# CB77-EI-Conversion-V1.net
KiCad netlist of a schematic drawn in EAGLE
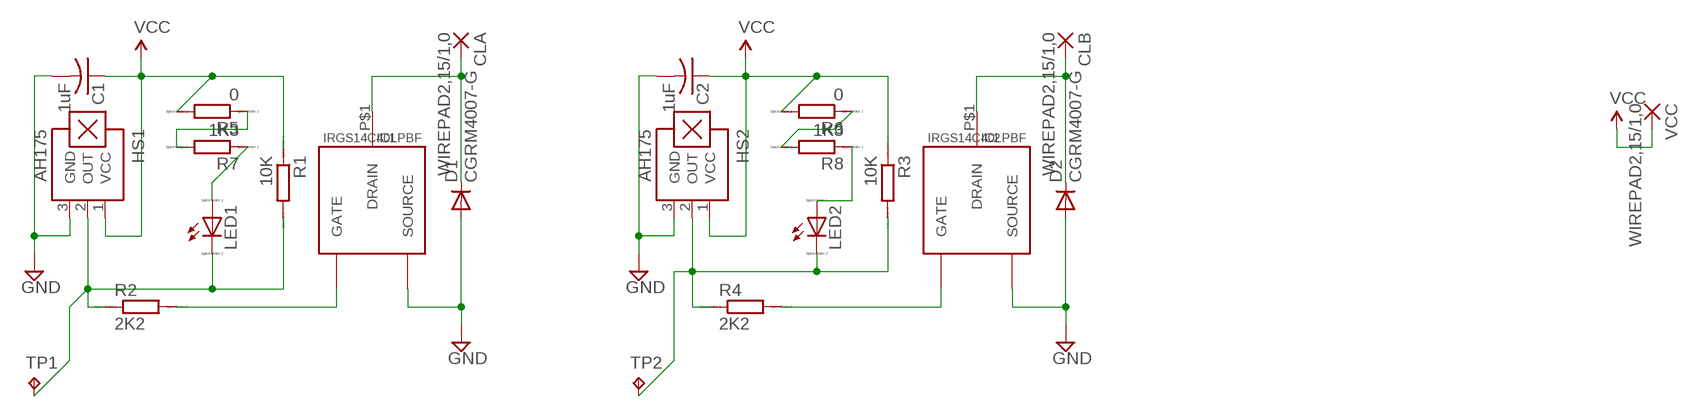
[diagram p0: schematic, sheet 1]

(export (version "E")
  (design (tool "Eeschema 10.0.6"))
  (components
    (comp (ref "C1")
      (value ".1uF")
      (footprint "eagle-import:C0603K")
      (libsource (lib "eagle-import") (part "C-USC0603K"))
    )
    (comp (ref "C2")
      (value ".1uF")
      (footprint "eagle-import:C0603K")
      (libsource (lib "eagle-import") (part "C-USC0603K"))
    )
    (comp (ref "CLA")
      (value "WIREPAD2,15/1,0")
      (footprint "eagle-import:2,15_1,0")
      (libsource (lib "eagle-import") (part "WIREPAD2,15/1,0"))
    )
    (comp (ref "CLB")
      (value "WIREPAD2,15/1,0")
      (footprint "eagle-import:2,15_1,0")
      (libsource (lib "eagle-import") (part "WIREPAD2,15/1,0"))
    )
    (comp (ref "D1")
      (value "CGRM4007-G")
      (footprint "eagle-import:SOD-123_MINI-SMA")
      (libsource (lib "eagle-import") (part "CGRM400-G7"))
    )
    (comp (ref "D2")
      (value "CGRM4007-G")
      (footprint "eagle-import:SOD-123_MINI-SMA")
      (libsource (lib "eagle-import") (part "CGRM400-G7"))
    )
    (comp (ref "HS1")
      (value "AH175")
      (footprint "eagle-import:SOT23-W")
      (fields (field (name "MF") "ALLEGRO MICROSYSTEMS, INC.") (field (name "MPN") "A1301ELHLT-T"))
      (libsource (lib "eagle-import") (part "A13?LH01"))
    )
    (comp (ref "HS2")
      (value "AH175")
      (footprint "eagle-import:SOT23-W")
      (fields (field (name "MF") "ALLEGRO MICROSYSTEMS, INC.") (field (name "MPN") "A1301ELHLT-T"))
      (libsource (lib "eagle-import") (part "A13?LH01"))
    )
    (comp (ref "IC1")
      (value "IRGS14C40LPBF")
      (footprint "eagle-import:TO-263AB")
      (libsource (lib "eagle-import") (part "IRGS14C40LPBF"))
    )
    (comp (ref "IC2")
      (value "IRGS14C40LPBF")
      (footprint "eagle-import:TO-263AB")
      (libsource (lib "eagle-import") (part "IRGS14C40LPBF"))
    )
    (comp (ref "LED1")
      (value "LED_E")
      (footprint "eagle-import:LED_1206")
      (libsource (lib "eagle-import") (part "LED_E"))
    )
    (comp (ref "LED2")
      (value "LED_E")
      (footprint "eagle-import:LED_1206")
      (libsource (lib "eagle-import") (part "LED_E"))
    )
    (comp (ref "R1")
      (value "10K")
      (footprint "eagle-import:R0805")
      (libsource (lib "eagle-import") (part "R"))
    )
    (comp (ref "R2")
      (value "2K2")
      (footprint "eagle-import:R0805")
      (libsource (lib "eagle-import") (part "R"))
    )
    (comp (ref "R3")
      (value "10K")
      (footprint "eagle-import:R0805")
      (libsource (lib "eagle-import") (part "R"))
    )
    (comp (ref "R4")
      (value "2K2")
      (footprint "eagle-import:R0805")
      (libsource (lib "eagle-import") (part "R"))
    )
    (comp (ref "R5") (value "0") (footprint "eagle-import:R0805") (libsource (lib "eagle-import") (part "R")))
    (comp (ref "R6") (value "0") (footprint "eagle-import:R0805") (libsource (lib "eagle-import") (part "R")))
    (comp (ref "R7")
      (value "1K3")
      (footprint "eagle-import:R0805")
      (libsource (lib "eagle-import") (part "R"))
    )
    (comp (ref "R8")
      (value "1K3")
      (footprint "eagle-import:R0805")
      (libsource (lib "eagle-import") (part "R"))
    )
    (comp (ref "TP1")
      (value "TPPAD1-17")
      (footprint "eagle-import:P1-17")
      (libsource (lib "eagle-import") (part "TPPAD1-17"))
    )
    (comp (ref "TP2")
      (value "TPPAD1-17")
      (footprint "eagle-import:P1-17")
      (libsource (lib "eagle-import") (part "TPPAD1-17"))
    )
    (comp (ref "VCC")
      (value "WIREPAD2,15/1,0")
      (footprint "eagle-import:2,15_1,0")
      (libsource (lib "eagle-import") (part "WIREPAD2,15/1,0"))
    )
  )
  (nets
    (net (code "1") (name "GND") (class "Default")
      (node (ref "C1") (pin "2") (pinfunction "2_2") (pintype "passive"))
      (node (ref "C2") (pin "2") (pinfunction "2_2") (pintype "passive"))
      (node (ref "D1") (pin "A") (pinfunction "A_A") (pintype "passive"))
      (node (ref "D2") (pin "A") (pinfunction "A_A") (pintype "passive"))
      (node (ref "HS1") (pin "3") (pinfunction "GND_3") (pintype "power_in"))
      (node (ref "HS2") (pin "3") (pinfunction "GND_3") (pintype "power_in"))
      (node (ref "IC1") (pin "P$3") (pinfunction "SOURCE_P$3") (pintype "bidirectional"))
      (node (ref "IC2") (pin "P$3") (pinfunction "SOURCE_P$3") (pintype "bidirectional"))
    )
    (net (code "2") (name "Net-(CLA-P)") (class "Default")
      (node (ref "CLA") (pin "1") (pinfunction "P_1") (pintype "passive"))
      (node (ref "D1") (pin "C") (pinfunction "C_C") (pintype "passive"))
      (node (ref "IC1") (pin "P$1") (pinfunction "DRAIN_P$1") (pintype "bidirectional"))
    )
    (net (code "3") (name "Net-(CLB-P)") (class "Default")
      (node (ref "CLB") (pin "1") (pinfunction "P_1") (pintype "passive"))
      (node (ref "D2") (pin "C") (pinfunction "C_C") (pintype "passive"))
      (node (ref "IC2") (pin "P$1") (pinfunction "DRAIN_P$1") (pintype "bidirectional"))
    )
    (net (code "4") (name "Net-(HS1-OUT)") (class "Default")
      (node (ref "HS1") (pin "2") (pinfunction "OUT_2") (pintype "output"))
      (node (ref "LED1") (pin "C") (pinfunction "C_C") (pintype "passive"))
      (node (ref "R1") (pin "2") (pinfunction "2_2") (pintype "passive"))
      (node (ref "R2") (pin "1") (pinfunction "1_1") (pintype "passive"))
      (node (ref "TP1") (pin "TP") (pinfunction "TP_TP") (pintype "input"))
    )
    (net (code "5") (name "Net-(HS2-OUT)") (class "Default")
      (node (ref "HS2") (pin "2") (pinfunction "OUT_2") (pintype "output"))
      (node (ref "LED2") (pin "C") (pinfunction "C_C") (pintype "passive"))
      (node (ref "R3") (pin "2") (pinfunction "2_2") (pintype "passive"))
      (node (ref "R4") (pin "1") (pinfunction "1_1") (pintype "passive"))
      (node (ref "TP2") (pin "TP") (pinfunction "TP_TP") (pintype "input"))
    )
    (net (code "6") (name "Net-(IC1-GATE)") (class "Default")
      (node (ref "IC1") (pin "P$2") (pinfunction "GATE_P$2") (pintype "bidirectional"))
      (node (ref "R2") (pin "2") (pinfunction "2_2") (pintype "passive"))
    )
    (net (code "7") (name "Net-(IC2-GATE)") (class "Default")
      (node (ref "IC2") (pin "P$2") (pinfunction "GATE_P$2") (pintype "bidirectional"))
      (node (ref "R4") (pin "2") (pinfunction "2_2") (pintype "passive"))
    )
    (net (code "8") (name "Net-(LED1-PadA)") (class "Default")
      (node (ref "LED1") (pin "A") (pinfunction "A_A") (pintype "passive"))
      (node (ref "R7") (pin "1") (pinfunction "1_1") (pintype "passive"))
    )
    (net (code "9") (name "Net-(LED2-PadA)") (class "Default")
      (node (ref "LED2") (pin "A") (pinfunction "A_A") (pintype "passive"))
      (node (ref "R8") (pin "1") (pinfunction "1_1") (pintype "passive"))
    )
    (net (code "10") (name "Net-(R5-Pad1)") (class "Default")
      (node (ref "R5") (pin "1") (pinfunction "1_1") (pintype "passive"))
      (node (ref "R7") (pin "2") (pinfunction "2_2") (pintype "passive"))
    )
    (net (code "11") (name "Net-(R6-Pad1)") (class "Default")
      (node (ref "R6") (pin "1") (pinfunction "1_1") (pintype "passive"))
      (node (ref "R8") (pin "2") (pinfunction "2_2") (pintype "passive"))
    )
    (net (code "12") (name "VCC") (class "Default")
      (node (ref "C1") (pin "1") (pinfunction "1_1") (pintype "passive"))
      (node (ref "C2") (pin "1") (pinfunction "1_1") (pintype "passive"))
      (node (ref "HS1") (pin "1") (pinfunction "VCC_1") (pintype "power_in"))
      (node (ref "HS2") (pin "1") (pinfunction "VCC_1") (pintype "power_in"))
      (node (ref "R1") (pin "1") (pinfunction "1_1") (pintype "passive"))
      (node (ref "R3") (pin "1") (pinfunction "1_1") (pintype "passive"))
      (node (ref "R5") (pin "2") (pinfunction "2_2") (pintype "passive"))
      (node (ref "R6") (pin "2") (pinfunction "2_2") (pintype "passive"))
      (node (ref "VCC") (pin "1") (pinfunction "P_1") (pintype "passive"))
    )
  )
)
